# Interface_BAT.net
KiCad netlist of a schematic drawn in EAGLE
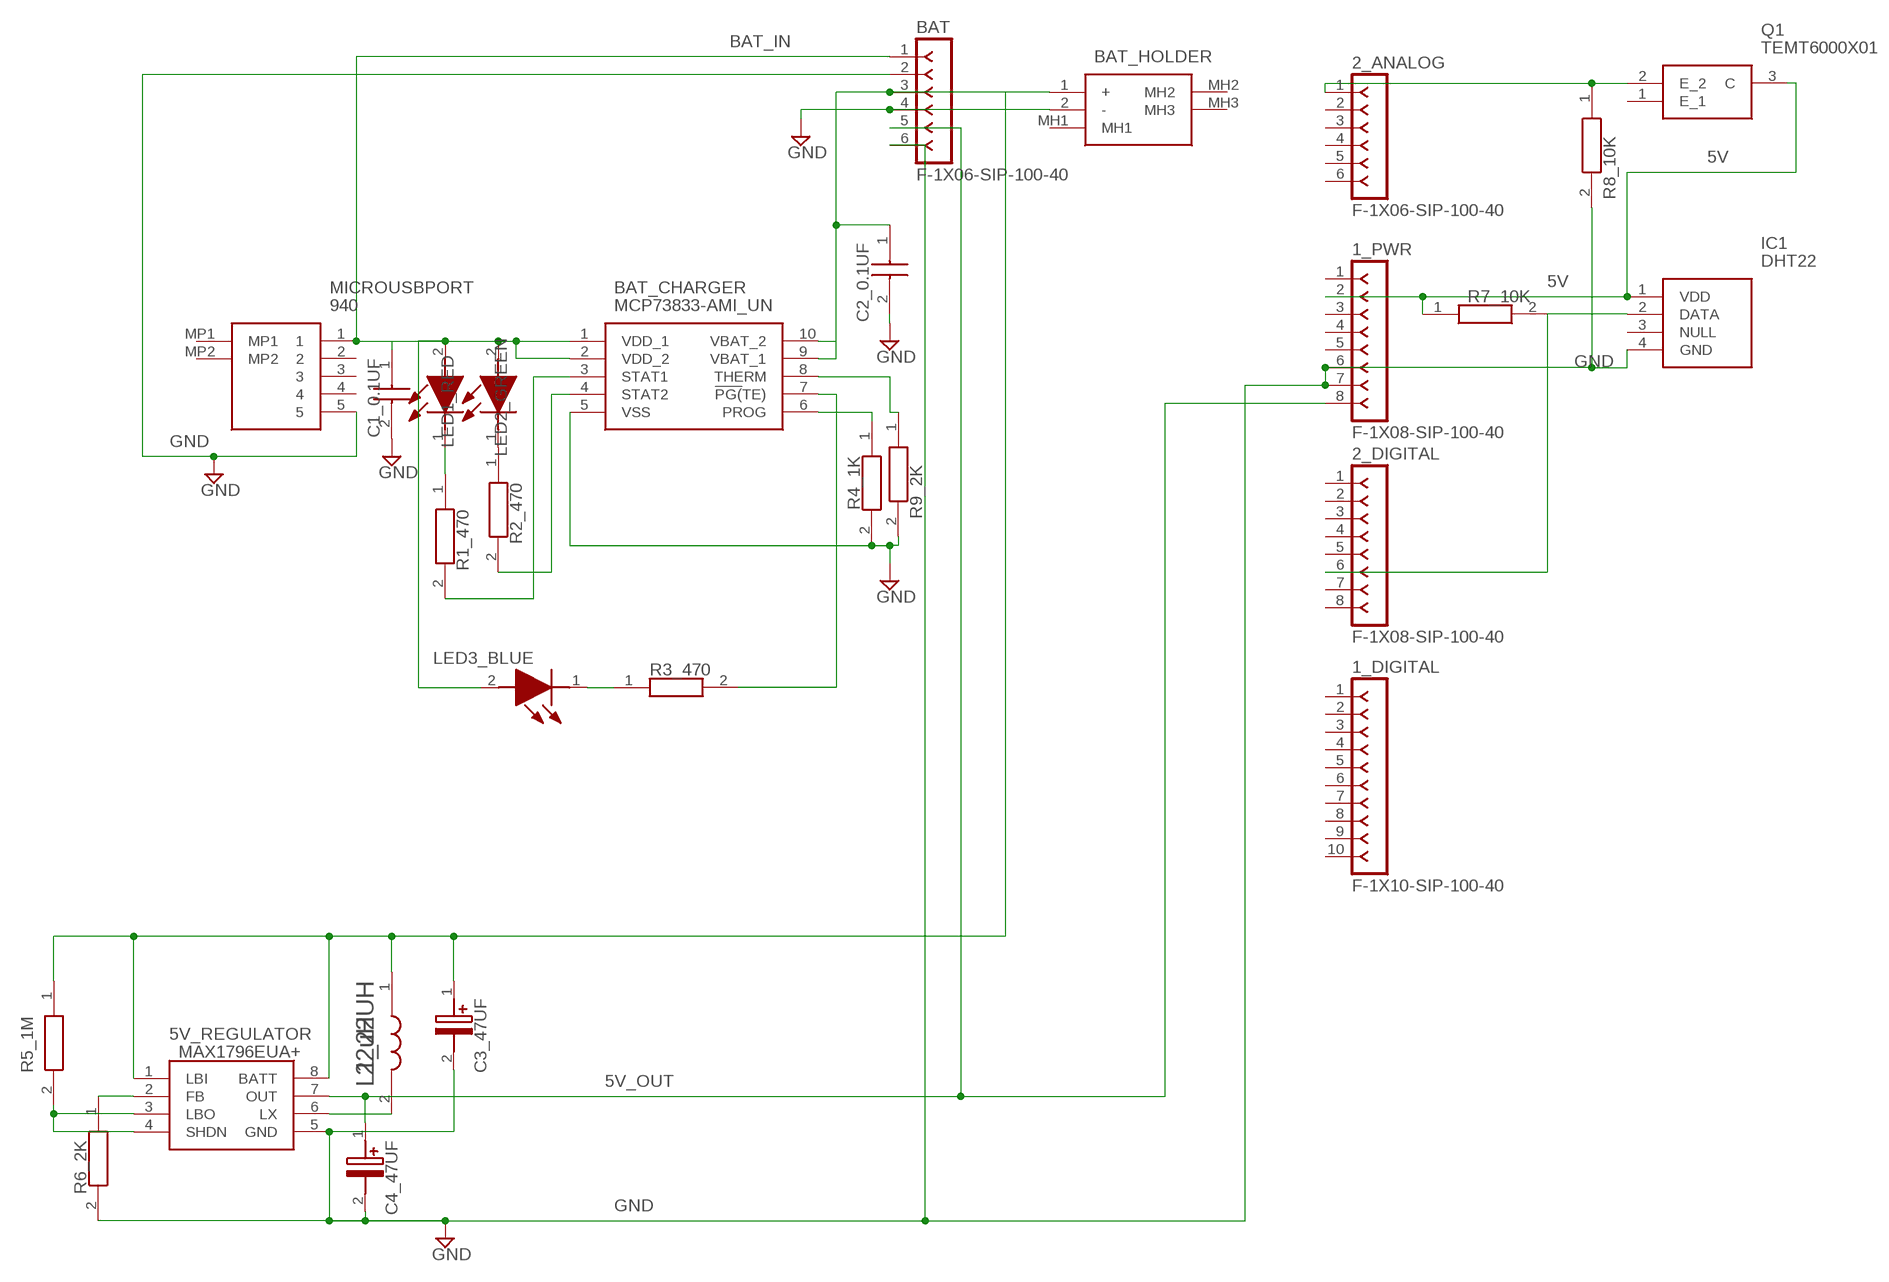
[diagram p0: schematic, sheet 1]

(export (version "E")
  (design (tool "Eeschema 10.0.6"))
  (components
    (comp (ref "1_DIGITAL")
      (value "F-1X10-SIP-100-40")
      (footprint "eagle-import:SIP-100-10-40")
      (libsource (lib "eagle-import") (part "F-1X10-SIP-100-40"))
    )
    (comp (ref "1_PWR")
      (value "F-1X08-SIP-100-40")
      (footprint "eagle-import:SIP-100-08-40")
      (libsource (lib "eagle-import") (part "F-1X08-SIP-100-40"))
    )
    (comp (ref "2_ANALOG")
      (value "F-1X06-SIP-100-40")
      (footprint "eagle-import:SIP-100-06-40")
      (libsource (lib "eagle-import") (part "F-1X06-SIP-100-40"))
    )
    (comp (ref "2_DIGITAL")
      (value "F-1X08-SIP-100-40")
      (footprint "eagle-import:SIP-100-08-40")
      (libsource (lib "eagle-import") (part "con-headers-jp-8pins_F-1X08-SIP-100-40"))
    )
    (comp (ref "5V_REGULATOR")
      (value "MAX1796EUA+")
      (footprint "eagle-import:SOP65P490X110-8N")
      (fields (field (name "MOUSER_PART_NUMBER") "700-MAX1796EUA"))
      (libsource (lib "eagle-import") (part "MAX1796EUA+"))
    )
    (comp (ref "BAT")
      (value "F-1X06-SIP-100-40")
      (footprint "eagle-import:SIP-100-06-40")
      (libsource (lib "eagle-import") (part "F-1X06-SIP-100-40"))
    )
    (comp (ref "BAT_CHARGER")
      (value "MCP73833-AMI_UN")
      (footprint "eagle-import:SOP50P490X110-10N")
      (fields
        (field (name "ARROW_PART_NUMBER") "MCP73833-AMI/UN")
        (field (name "MOUSER_PART_NUMBER") "579-MCP73833-AMI/UN")
      )
      (libsource (lib "eagle-import") (part "MCP73833-AMI_UN"))
    )
    (comp (ref "BAT_HOLDER")
      (value "1043")
      (footprint "eagle-import:1043")
      (fields (field (name "MOUSER_PART_NUMBER") "534-1043"))
      (libsource (lib "eagle-import") (part "1043"))
    )
    (comp (ref "C1_0.1UF")
      (value "C0805C104J5RACTU")
      (footprint "eagle-import:CAPC2012X88N")
      (fields (field (name "MOUSER_PART_NUMBER") "80-C0805C104J5R"))
      (libsource (lib "eagle-import") (part "C0805C104J5RACTU"))
    )
    (comp (ref "C2_0.1UF")
      (value "C0805C104J5RACTU")
      (footprint "eagle-import:CAPC2012X88N")
      (fields (field (name "MOUSER_PART_NUMBER") "80-C0805C104J5R"))
      (libsource (lib "eagle-import") (part "C0805C104J5RACTU"))
    )
    (comp (ref "C3_47UF")
      (value "10TPB47M")
      (footprint "eagle-import:CAPPM3528X210N")
      (fields (field (name "MOUSER_PART_NUMBER") "667-10TPB47M"))
      (libsource (lib "eagle-import") (part "10TPB47M"))
    )
    (comp (ref "C4_47UF")
      (value "10TPB47M")
      (footprint "eagle-import:CAPPM3528X210N")
      (fields (field (name "MOUSER_PART_NUMBER") "667-10TPB47M"))
      (libsource (lib "eagle-import") (part "10TPB47M"))
    )
    (comp (ref "IC1")
      (value "DHT22")
      (footprint "eagle-import:DHT22")
      (libsource (lib "eagle-import") (part "DHT22"))
    )
    (comp (ref "L1_22UH")
      (value "COILCRAFT_LPS4018-223MRBCOILCRAFT_LPS4018-223MRB_0_0")
      (footprint "eagle-import:COILCRAFT_LPS4018-223MRB_0")
      (fields
        (field (name "MF") "Coilcraft")
        (field (name "MOUSER_PART_NUMBER") "994-LPS4018-223MRB")
        (field (name "MPN") "LPS4018-223MRB")
      )
      (libsource (lib "eagle-import") (part "COILCRAFT_LPS4018-223MRBCOILCRAFT_LPS4018-223MRB_0_0"))
    )
    (comp (ref "LED1_RED")
      (value "KP-2012CGCK")
      (footprint "eagle-import:LEDC2012X110N")
      (libsource (lib "eagle-import") (part "KP-2012CGCK"))
    )
    (comp (ref "LED2_GREEN")
      (value "KP-2012CGCK")
      (footprint "eagle-import:LEDC2012X110N")
      (libsource (lib "eagle-import") (part "KP-2012CGCK"))
    )
    (comp (ref "LED3_BLUE")
      (value "KP-2012CGCK")
      (footprint "eagle-import:LEDC2012X110N")
      (libsource (lib "eagle-import") (part "KP-2012CGCK"))
    )
    (comp (ref "MICROUSBPORT")
      (value "940")
      (footprint "eagle-import:940")
      (fields (field (name "MOUSER_PART_NUMBER") "534-940"))
      (libsource (lib "eagle-import") (part "940"))
    )
    (comp (ref "Q1")
      (value "TEMT6000X01")
      (footprint "eagle-import:TEMT6000X01")
      (fields (field (name "MOUSER_PART_NUMBER") "78-TEMT6000"))
      (libsource (lib "eagle-import") (part "TEMT6000X01"))
    )
    (comp (ref "R1_470")
      (value "CRCW0805470RFKEA")
      (footprint "eagle-import:RESC2012X50N")
      (fields (field (name "MOUSER_PART_NUMBER") "71-CRCW0805-470-E3"))
      (libsource (lib "eagle-import") (part "CRCW0805470RFKEA"))
    )
    (comp (ref "R2_470")
      (value "CRCW0805470RFKEA")
      (footprint "eagle-import:RESC2012X50N")
      (fields (field (name "MOUSER_PART_NUMBER") "71-CRCW0805-470-E3"))
      (libsource (lib "eagle-import") (part "CRCW0805470RFKEA"))
    )
    (comp (ref "R3_470")
      (value "CRCW0805470RFKEA")
      (footprint "eagle-import:RESC2012X50N")
      (fields (field (name "MOUSER_PART_NUMBER") "71-CRCW0805-470-E3"))
      (libsource (lib "eagle-import") (part "CRCW0805470RFKEA"))
    )
    (comp (ref "R4_1K")
      (value "CRCW08051K00FKEA")
      (footprint "eagle-import:RESC2012X50N")
      (fields (field (name "MOUSER_PART_NUMBER") "71-CRCW0805-1.0K-E3"))
      (libsource (lib "eagle-import") (part "CRCW08051K00FKEA"))
    )
    (comp (ref "R5_1M")
      (value "ERA6AEB105V")
      (footprint "eagle-import:RESC2012X60N")
      (libsource (lib "eagle-import") (part "ERA6AEB105V"))
    )
    (comp (ref "R6_2K")
      (value "CRCW08052K00FKEA")
      (footprint "eagle-import:RESC2012X50N")
      (fields (field (name "MOUSER_PART_NUMBER") "71-CRCW0805-2.0K-E3"))
      (libsource (lib "eagle-import") (part "CRCW08052K00FKEA"))
    )
    (comp (ref "R7_10K")
      (value "ERJ6GEYJ103V")
      (footprint "eagle-import:RESC2012X70N")
      (libsource (lib "eagle-import") (part "ERJ6GEYJ103V"))
    )
    (comp (ref "R8_10K")
      (value "ERJ6GEYJ103V")
      (footprint "eagle-import:RESC2012X70N")
      (libsource (lib "eagle-import") (part "ERJ6GEYJ103V"))
    )
    (comp (ref "R9_2K")
      (value "CRCW08052K00FKEA")
      (footprint "eagle-import:RESC2012X50N")
      (fields (field (name "MOUSER_PART_NUMBER") "71-CRCW0805-2.0K-E3"))
      (libsource (lib "eagle-import") (part "CRCW08052K00FKEA"))
    )
  )
  (nets
    (net (code "1") (name "/5V") (class "Default")
      (node (ref "1_PWR") (pin "2") (pinfunction "2_2") (pintype "passive"))
      (node (ref "IC1") (pin "1") (pinfunction "VDD_1") (pintype "bidirectional"))
      (node (ref "Q1") (pin "3") (pinfunction "C_3") (pintype "bidirectional"))
      (node (ref "R7_10K") (pin "1") (pinfunction "1_1") (pintype "bidirectional"))
    )
    (net (code "2") (name "/5V_OUT") (class "Default")
      (node (ref "1_PWR") (pin "8") (pinfunction "8_8") (pintype "passive"))
      (node (ref "5V_REGULATOR") (pin "7") (pinfunction "OUT_7") (pintype "bidirectional"))
      (node (ref "BAT") (pin "5") (pinfunction "5_5") (pintype "passive"))
      (node (ref "C4_47UF") (pin "1") (pinfunction "+_1") (pintype "bidirectional"))
    )
    (net (code "3") (name "/BAT_IN") (class "Default")
      (node (ref "BAT") (pin "1") (pinfunction "1_1") (pintype "passive"))
      (node (ref "BAT_CHARGER") (pin "1") (pinfunction "VDD_1_1") (pintype "bidirectional"))
      (node (ref "BAT_CHARGER") (pin "2") (pinfunction "VDD_2_2") (pintype "bidirectional"))
      (node (ref "C1_0.1UF") (pin "1") (pinfunction "1_1") (pintype "bidirectional"))
      (node (ref "LED1_RED") (pin "2") (pinfunction "A_2") (pintype "bidirectional"))
      (node (ref "LED2_GREEN") (pin "2") (pinfunction "A_2") (pintype "bidirectional"))
      (node (ref "LED3_BLUE") (pin "2") (pinfunction "A_2") (pintype "bidirectional"))
      (node (ref "MICROUSBPORT") (pin "1") (pinfunction "1_1") (pintype "bidirectional"))
    )
    (net (code "4") (name "GND") (class "Default")
      (node (ref "1_PWR") (pin "6") (pinfunction "6_6") (pintype "passive"))
      (node (ref "1_PWR") (pin "7") (pinfunction "7_7") (pintype "passive"))
      (node (ref "5V_REGULATOR") (pin "5") (pinfunction "GND_5") (pintype "bidirectional"))
      (node (ref "BAT") (pin "2") (pinfunction "2_2") (pintype "passive"))
      (node (ref "BAT") (pin "4") (pinfunction "4_4") (pintype "passive"))
      (node (ref "BAT") (pin "6") (pinfunction "6_6") (pintype "passive"))
      (node (ref "BAT_CHARGER") (pin "5") (pinfunction "VSS_5") (pintype "bidirectional"))
      (node (ref "BAT_HOLDER") (pin "2") (pinfunction "-_2") (pintype "bidirectional"))
      (node (ref "C1_0.1UF") (pin "2") (pinfunction "2_2") (pintype "bidirectional"))
      (node (ref "C2_0.1UF") (pin "2") (pinfunction "2_2") (pintype "bidirectional"))
      (node (ref "C3_47UF") (pin "2") (pinfunction "-_2") (pintype "bidirectional"))
      (node (ref "C4_47UF") (pin "2") (pinfunction "-_2") (pintype "bidirectional"))
      (node (ref "IC1") (pin "4") (pinfunction "GND_4") (pintype "bidirectional"))
      (node (ref "MICROUSBPORT") (pin "5") (pinfunction "5_5") (pintype "bidirectional"))
      (node (ref "R4_1K") (pin "2") (pinfunction "2_2") (pintype "bidirectional"))
      (node (ref "R6_2K") (pin "2") (pinfunction "2_2") (pintype "bidirectional"))
      (node (ref "R8_10K") (pin "2") (pinfunction "2_2") (pintype "bidirectional"))
      (node (ref "R9_2K") (pin "2") (pinfunction "2_2") (pintype "bidirectional"))
    )
    (net (code "5") (name "Net-(5V_REGULATOR-BATT)") (class "Default")
      (node (ref "5V_REGULATOR") (pin "1") (pinfunction "LBI_1") (pintype "bidirectional"))
      (node (ref "5V_REGULATOR") (pin "8") (pinfunction "BATT_8") (pintype "bidirectional"))
      (node (ref "BAT") (pin "3") (pinfunction "3_3") (pintype "passive"))
      (node (ref "BAT_CHARGER") (pin "10") (pinfunction "VBAT_2_10") (pintype "bidirectional"))
      (node (ref "BAT_CHARGER") (pin "9") (pinfunction "VBAT_1_9") (pintype "bidirectional"))
      (node (ref "BAT_HOLDER") (pin "1") (pinfunction "+_1") (pintype "bidirectional"))
      (node (ref "C2_0.1UF") (pin "1") (pinfunction "1_1") (pintype "bidirectional"))
      (node (ref "C3_47UF") (pin "1") (pinfunction "+_1") (pintype "bidirectional"))
      (node (ref "L1_22UH") (pin "1") (pinfunction "1_1") (pintype "passive"))
      (node (ref "R5_1M") (pin "1") (pinfunction "1_1") (pintype "bidirectional"))
    )
    (net (code "6") (name "Net-(5V_REGULATOR-FB)") (class "Default")
      (node (ref "5V_REGULATOR") (pin "2") (pinfunction "FB_2") (pintype "bidirectional"))
      (node (ref "R6_2K") (pin "1") (pinfunction "1_1") (pintype "bidirectional"))
    )
    (net (code "7") (name "Net-(5V_REGULATOR-LBO)") (class "Default")
      (node (ref "5V_REGULATOR") (pin "3") (pinfunction "LBO_3") (pintype "bidirectional"))
      (node (ref "5V_REGULATOR") (pin "4") (pinfunction "SHDN_4") (pintype "bidirectional"))
      (node (ref "R5_1M") (pin "2") (pinfunction "2_2") (pintype "bidirectional"))
    )
    (net (code "8") (name "Net-(5V_REGULATOR-LX)") (class "Default")
      (node (ref "5V_REGULATOR") (pin "6") (pinfunction "LX_6") (pintype "bidirectional"))
      (node (ref "L1_22UH") (pin "2") (pinfunction "2_2") (pintype "passive"))
    )
    (net (code "9") (name "Net-(BAT_CHARGER-PROG)") (class "Default")
      (node (ref "BAT_CHARGER") (pin "6") (pinfunction "PROG_6") (pintype "bidirectional"))
      (node (ref "R4_1K") (pin "1") (pinfunction "1_1") (pintype "bidirectional"))
    )
    (net (code "10") (name "Net-(BAT_CHARGER-STAT1)") (class "Default")
      (node (ref "BAT_CHARGER") (pin "3") (pinfunction "STAT1_3") (pintype "bidirectional"))
      (node (ref "R1_470") (pin "2") (pinfunction "2_2") (pintype "bidirectional"))
    )
    (net (code "11") (name "Net-(BAT_CHARGER-STAT2)") (class "Default")
      (node (ref "BAT_CHARGER") (pin "4") (pinfunction "STAT2_4") (pintype "bidirectional"))
      (node (ref "R2_470") (pin "2") (pinfunction "2_2") (pintype "bidirectional"))
    )
    (net (code "12") (name "Net-(BAT_CHARGER-THERM)") (class "Default")
      (node (ref "BAT_CHARGER") (pin "8") (pinfunction "THERM_8") (pintype "bidirectional"))
      (node (ref "R9_2K") (pin "1") (pinfunction "1_1") (pintype "bidirectional"))
    )
    (net (code "13") (name "Net-(BAT_CHARGER-~{PG(}TE))") (class "Default")
      (node (ref "BAT_CHARGER") (pin "7") (pinfunction "~{PG(}TE)_7") (pintype "bidirectional"))
      (node (ref "R3_470") (pin "2") (pinfunction "2_2") (pintype "bidirectional"))
    )
    (net (code "14") (name "Net-(IC1-DATA)") (class "Default")
      (node (ref "2_DIGITAL") (pin "6") (pinfunction "6_6") (pintype "passive"))
      (node (ref "IC1") (pin "2") (pinfunction "DATA_2") (pintype "bidirectional"))
      (node (ref "R7_10K") (pin "2") (pinfunction "2_2") (pintype "bidirectional"))
    )
    (net (code "15") (name "Net-(LED1_RED-K)") (class "Default")
      (node (ref "LED1_RED") (pin "1") (pinfunction "K_1") (pintype "bidirectional"))
      (node (ref "R1_470") (pin "1") (pinfunction "1_1") (pintype "bidirectional"))
    )
    (net (code "16") (name "Net-(LED2_GREEN-K)") (class "Default")
      (node (ref "LED2_GREEN") (pin "1") (pinfunction "K_1") (pintype "bidirectional"))
      (node (ref "R2_470") (pin "1") (pinfunction "1_1") (pintype "bidirectional"))
    )
    (net (code "17") (name "Net-(LED3_BLUE-K)") (class "Default")
      (node (ref "LED3_BLUE") (pin "1") (pinfunction "K_1") (pintype "bidirectional"))
      (node (ref "R3_470") (pin "1") (pinfunction "1_1") (pintype "bidirectional"))
    )
    (net (code "18") (name "Net-(Q1-E_2)") (class "Default")
      (node (ref "2_ANALOG") (pin "1") (pinfunction "1_1") (pintype "passive"))
      (node (ref "Q1") (pin "2") (pinfunction "E_2_2") (pintype "bidirectional"))
      (node (ref "R8_10K") (pin "1") (pinfunction "1_1") (pintype "bidirectional"))
    )
    (net (code "19") (name "unconnected-(1_DIGITAL-Pad1)") (class "Default")
      (node (ref "1_DIGITAL") (pin "1") (pinfunction "1_1") (pintype "passive"))
    )
    (net (code "20") (name "unconnected-(1_DIGITAL-Pad2)") (class "Default")
      (node (ref "1_DIGITAL") (pin "2") (pinfunction "2_2") (pintype "passive"))
    )
    (net (code "21") (name "unconnected-(1_DIGITAL-Pad3)") (class "Default")
      (node (ref "1_DIGITAL") (pin "3") (pinfunction "3_3") (pintype "passive"))
    )
    (net (code "22") (name "unconnected-(1_DIGITAL-Pad4)") (class "Default")
      (node (ref "1_DIGITAL") (pin "4") (pinfunction "4_4") (pintype "passive"))
    )
    (net (code "23") (name "unconnected-(1_DIGITAL-Pad5)") (class "Default")
      (node (ref "1_DIGITAL") (pin "5") (pinfunction "5_5") (pintype "passive"))
    )
    (net (code "24") (name "unconnected-(1_DIGITAL-Pad6)") (class "Default")
      (node (ref "1_DIGITAL") (pin "6") (pinfunction "6_6") (pintype "passive"))
    )
    (net (code "25") (name "unconnected-(1_DIGITAL-Pad7)") (class "Default")
      (node (ref "1_DIGITAL") (pin "7") (pinfunction "7_7") (pintype "passive"))
    )
    (net (code "26") (name "unconnected-(1_DIGITAL-Pad8)") (class "Default")
      (node (ref "1_DIGITAL") (pin "8") (pinfunction "8_8") (pintype "passive"))
    )
    (net (code "27") (name "unconnected-(1_DIGITAL-Pad9)") (class "Default")
      (node (ref "1_DIGITAL") (pin "9") (pinfunction "9_9") (pintype "passive"))
    )
    (net (code "28") (name "unconnected-(1_DIGITAL-Pad10)") (class "Default")
      (node (ref "1_DIGITAL") (pin "10") (pinfunction "10_10") (pintype "passive"))
    )
    (net (code "29") (name "unconnected-(1_PWR-Pad1)") (class "Default")
      (node (ref "1_PWR") (pin "1") (pinfunction "1_1") (pintype "passive"))
    )
    (net (code "30") (name "unconnected-(1_PWR-Pad3)") (class "Default")
      (node (ref "1_PWR") (pin "3") (pinfunction "3_3") (pintype "passive"))
    )
    (net (code "31") (name "unconnected-(1_PWR-Pad4)") (class "Default")
      (node (ref "1_PWR") (pin "4") (pinfunction "4_4") (pintype "passive"))
    )
    (net (code "32") (name "unconnected-(1_PWR-Pad5)") (class "Default")
      (node (ref "1_PWR") (pin "5") (pinfunction "5_5") (pintype "passive"))
    )
    (net (code "33") (name "unconnected-(2_ANALOG-Pad2)") (class "Default")
      (node (ref "2_ANALOG") (pin "2") (pinfunction "2_2") (pintype "passive"))
    )
    (net (code "34") (name "unconnected-(2_ANALOG-Pad3)") (class "Default")
      (node (ref "2_ANALOG") (pin "3") (pinfunction "3_3") (pintype "passive"))
    )
    (net (code "35") (name "unconnected-(2_ANALOG-Pad4)") (class "Default")
      (node (ref "2_ANALOG") (pin "4") (pinfunction "4_4") (pintype "passive"))
    )
    (net (code "36") (name "unconnected-(2_ANALOG-Pad5)") (class "Default")
      (node (ref "2_ANALOG") (pin "5") (pinfunction "5_5") (pintype "passive"))
    )
    (net (code "37") (name "unconnected-(2_ANALOG-Pad6)") (class "Default")
      (node (ref "2_ANALOG") (pin "6") (pinfunction "6_6") (pintype "passive"))
    )
    (net (code "38") (name "unconnected-(2_DIGITAL-Pad1)") (class "Default")
      (node (ref "2_DIGITAL") (pin "1") (pinfunction "1_1") (pintype "passive"))
    )
    (net (code "39") (name "unconnected-(2_DIGITAL-Pad2)") (class "Default")
      (node (ref "2_DIGITAL") (pin "2") (pinfunction "2_2") (pintype "passive"))
    )
    (net (code "40") (name "unconnected-(2_DIGITAL-Pad3)") (class "Default")
      (node (ref "2_DIGITAL") (pin "3") (pinfunction "3_3") (pintype "passive"))
    )
    (net (code "41") (name "unconnected-(2_DIGITAL-Pad4)") (class "Default")
      (node (ref "2_DIGITAL") (pin "4") (pinfunction "4_4") (pintype "passive"))
    )
    (net (code "42") (name "unconnected-(2_DIGITAL-Pad5)") (class "Default")
      (node (ref "2_DIGITAL") (pin "5") (pinfunction "5_5") (pintype "passive"))
    )
    (net (code "43") (name "unconnected-(2_DIGITAL-Pad7)") (class "Default")
      (node (ref "2_DIGITAL") (pin "7") (pinfunction "7_7") (pintype "passive"))
    )
    (net (code "44") (name "unconnected-(2_DIGITAL-Pad8)") (class "Default")
      (node (ref "2_DIGITAL") (pin "8") (pinfunction "8_8") (pintype "passive"))
    )
    (net (code "45") (name "unconnected-(BAT_HOLDER-PadMH1)") (class "Default")
      (node (ref "BAT_HOLDER") (pin "MH1") (pinfunction "MH1_MH1") (pintype "bidirectional"))
    )
    (net (code "46") (name "unconnected-(BAT_HOLDER-PadMH2)") (class "Default")
      (node (ref "BAT_HOLDER") (pin "MH2") (pinfunction "MH2_MH2") (pintype "bidirectional"))
    )
    (net (code "47") (name "unconnected-(BAT_HOLDER-PadMH3)") (class "Default")
      (node (ref "BAT_HOLDER") (pin "MH3") (pinfunction "MH3_MH3") (pintype "bidirectional"))
    )
    (net (code "48") (name "unconnected-(IC1-NULL-Pad3)") (class "Default")
      (node (ref "IC1") (pin "3") (pinfunction "NULL_3") (pintype "bidirectional"))
    )
    (net (code "49") (name "unconnected-(MICROUSBPORT-Pad2)") (class "Default")
      (node (ref "MICROUSBPORT") (pin "2") (pinfunction "2_2") (pintype "bidirectional"))
    )
    (net (code "50") (name "unconnected-(MICROUSBPORT-Pad3)") (class "Default")
      (node (ref "MICROUSBPORT") (pin "3") (pinfunction "3_3") (pintype "bidirectional"))
    )
    (net (code "51") (name "unconnected-(MICROUSBPORT-Pad4)") (class "Default")
      (node (ref "MICROUSBPORT") (pin "4") (pinfunction "4_4") (pintype "bidirectional"))
    )
    (net (code "52") (name "unconnected-(MICROUSBPORT-PadMP1)") (class "Default")
      (node (ref "MICROUSBPORT") (pin "MP1") (pinfunction "MP1_MP1") (pintype "bidirectional"))
    )
    (net (code "53") (name "unconnected-(MICROUSBPORT-PadMP2)") (class "Default")
      (node (ref "MICROUSBPORT") (pin "MP2") (pinfunction "MP2_MP2") (pintype "bidirectional"))
    )
    (net (code "54") (name "unconnected-(Q1-E_1-Pad1)") (class "Default")
      (node (ref "Q1") (pin "1") (pinfunction "E_1_1") (pintype "bidirectional"))
    )
  )
)
